# mems_quart_board_SPH0645LM4H-B.net
KiCad netlist of a schematic drawn in EAGLE
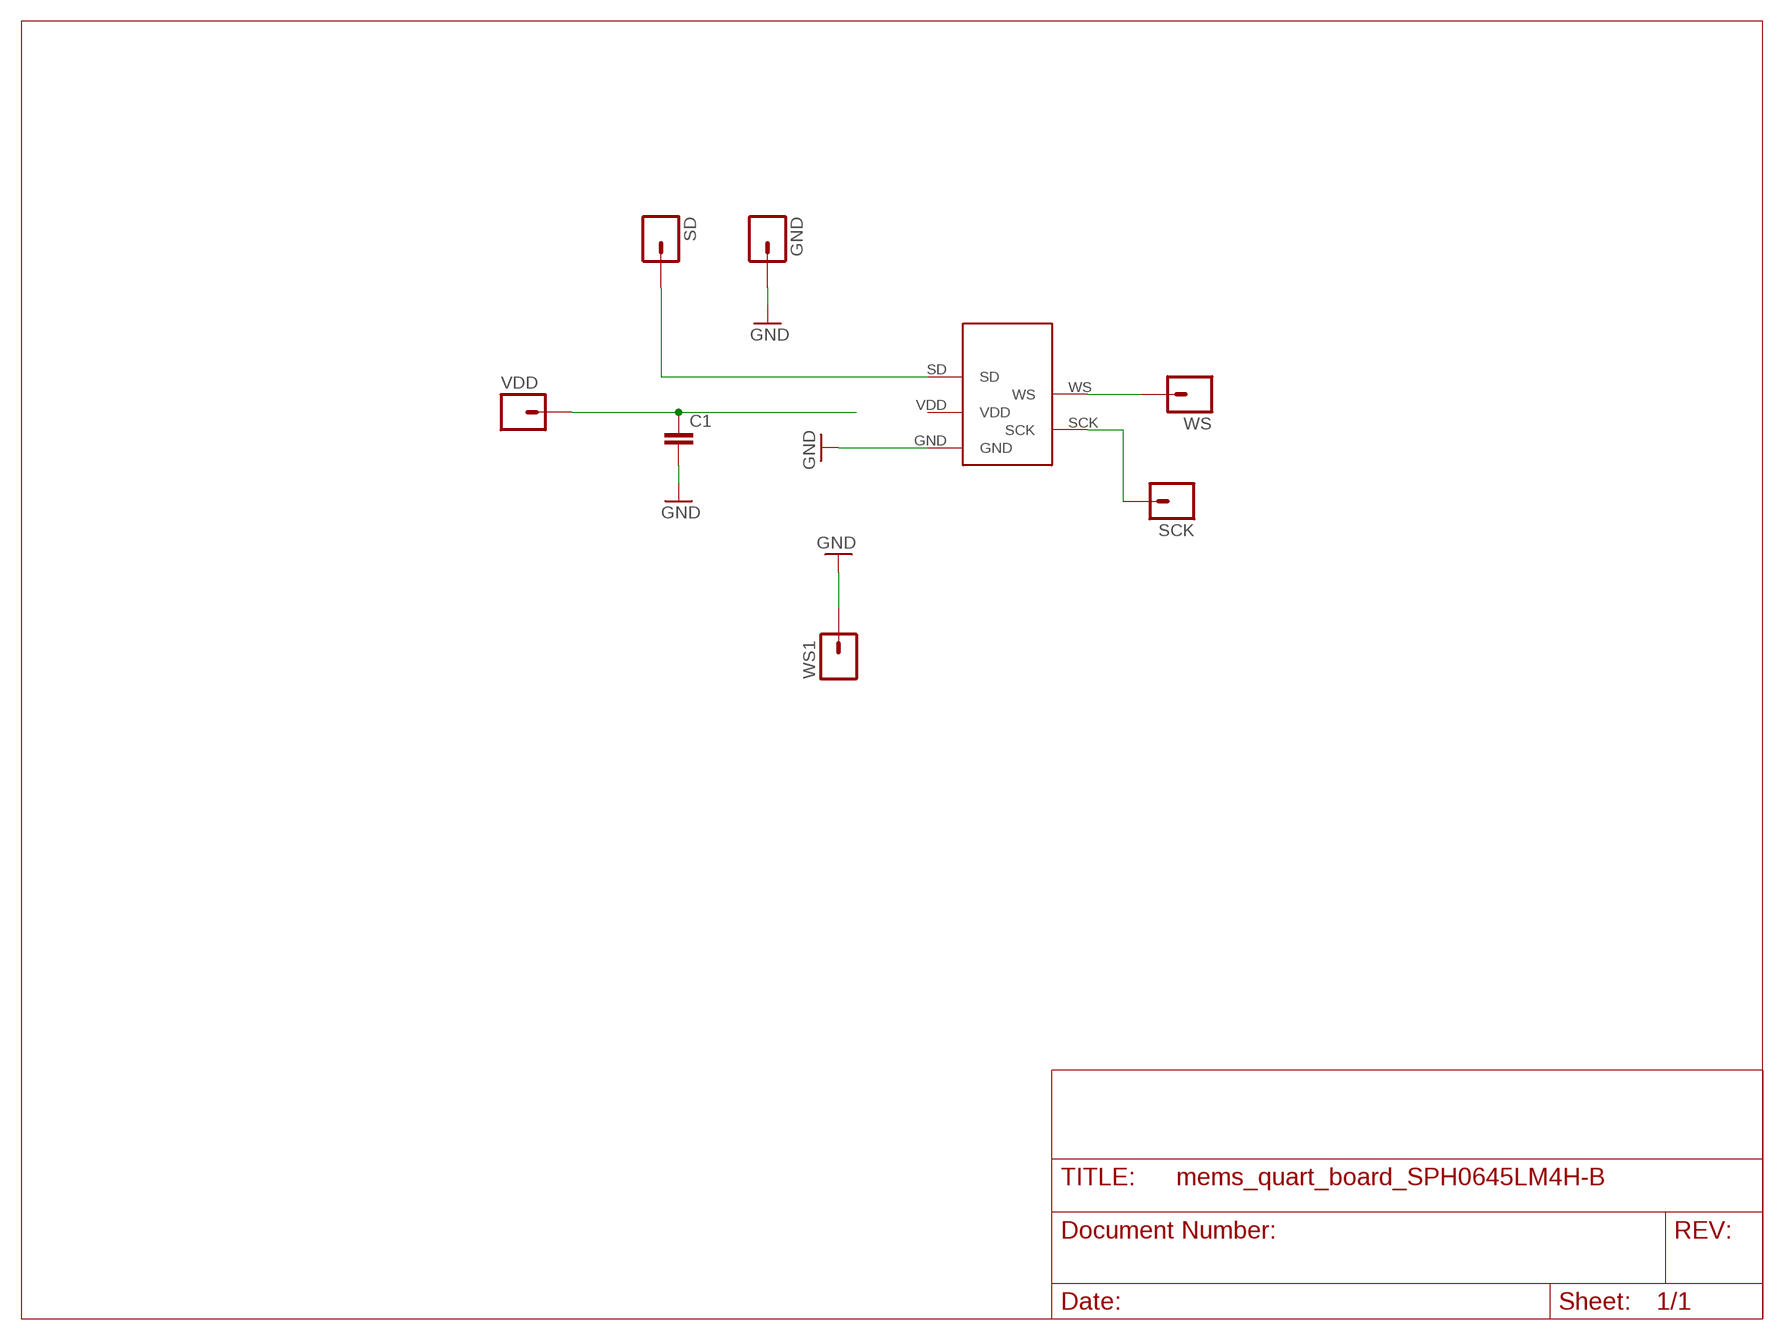
[diagram p0: schematic, sheet 1]

(export (version "E")
  (design (tool "Eeschema 10.0.6"))
  (components
    (comp (ref "C1")
      (value "0.1UF-16V(+-10%)(0402)")
      (footprint "eagle-import:0402-CAP")
      (libsource (lib "eagle-import") (part "0.1UF-16V(+-10%)(0402)"))
    )
    (comp (ref "GND")
      (value "M01PTH_NO_SILK_YES_STOP")
      (footprint "eagle-import:1X01_NO_SILK")
      (libsource (lib "eagle-import") (part "CM-SparkFun-Connectors-2_M01PTH_NO_SILK_YES_STOP"))
    )
    (comp (ref "SCK")
      (value "M01NOSILK-KIT")
      (footprint "eagle-import:1X01NS-KIT")
      (libsource (lib "eagle-import") (part "M01NOSILK-KIT"))
    )
    (comp (ref "SD")
      (value "M01NOSILK-KIT")
      (footprint "eagle-import:1X01NS-KIT")
      (libsource (lib "eagle-import") (part "M01NOSILK-KIT"))
    )
    (comp (ref "U$2")
      (value "MEM_SPH0645LM4H-B")
      (footprint "eagle-import:MEMS_SPH0645LM4H-B")
      (libsource (lib "eagle-import") (part "MEM_SPH0645LM4H-B"))
    )
    (comp (ref "VDD")
      (value "M01NOSILK-KIT")
      (footprint "eagle-import:1X01NS-KIT")
      (libsource (lib "eagle-import") (part "M01NOSILK-KIT"))
    )
    (comp (ref "WS")
      (value "M01NOSILK-KIT")
      (footprint "eagle-import:1X01NS-KIT")
      (libsource (lib "eagle-import") (part "M01NOSILK-KIT"))
    )
    (comp (ref "WS1")
      (value "M01NOSILK-KIT")
      (footprint "eagle-import:1X01NS-KIT")
      (libsource (lib "eagle-import") (part "M01NOSILK-KIT"))
    )
  )
  (nets
    (net (code "1") (name "/VDD") (class "Default")
      (node (ref "U$2") (pin "VDD") (pinfunction "VDD_VDD") (pintype "power_in"))
    )
    (net (code "2") (name "GND") (class "Default")
      (node (ref "C1") (pin "2") (pinfunction "2_2") (pintype "passive"))
      (node (ref "GND") (pin "1") (pinfunction "1_1") (pintype "passive"))
      (node (ref "U$2") (pin "GND") (pinfunction "GND_GND") (pintype "input"))
      (node (ref "WS1") (pin "1") (pinfunction "1_1") (pintype "passive"))
    )
    (net (code "3") (name "Net-(C1-Pad1)") (class "Default")
      (node (ref "C1") (pin "1") (pinfunction "1_1") (pintype "passive"))
      (node (ref "VDD") (pin "1") (pinfunction "1_1") (pintype "passive"))
    )
    (net (code "4") (name "Net-(SCK-Pad1)") (class "Default")
      (node (ref "SCK") (pin "1") (pinfunction "1_1") (pintype "passive"))
      (node (ref "U$2") (pin "SCK") (pinfunction "SCK_SCK") (pintype "input"))
    )
    (net (code "5") (name "Net-(SD-Pad1)") (class "Default")
      (node (ref "SD") (pin "1") (pinfunction "1_1") (pintype "passive"))
      (node (ref "U$2") (pin "SD") (pinfunction "SD_SD") (pintype "output"))
    )
    (net (code "6") (name "Net-(U$2-PadWS)") (class "Default")
      (node (ref "U$2") (pin "WS") (pinfunction "WS_WS") (pintype "input"))
      (node (ref "WS") (pin "1") (pinfunction "1_1") (pintype "passive"))
    )
  )
)
